# SwitchRegTestBoard.net
KiCad netlist of a schematic drawn in EAGLE
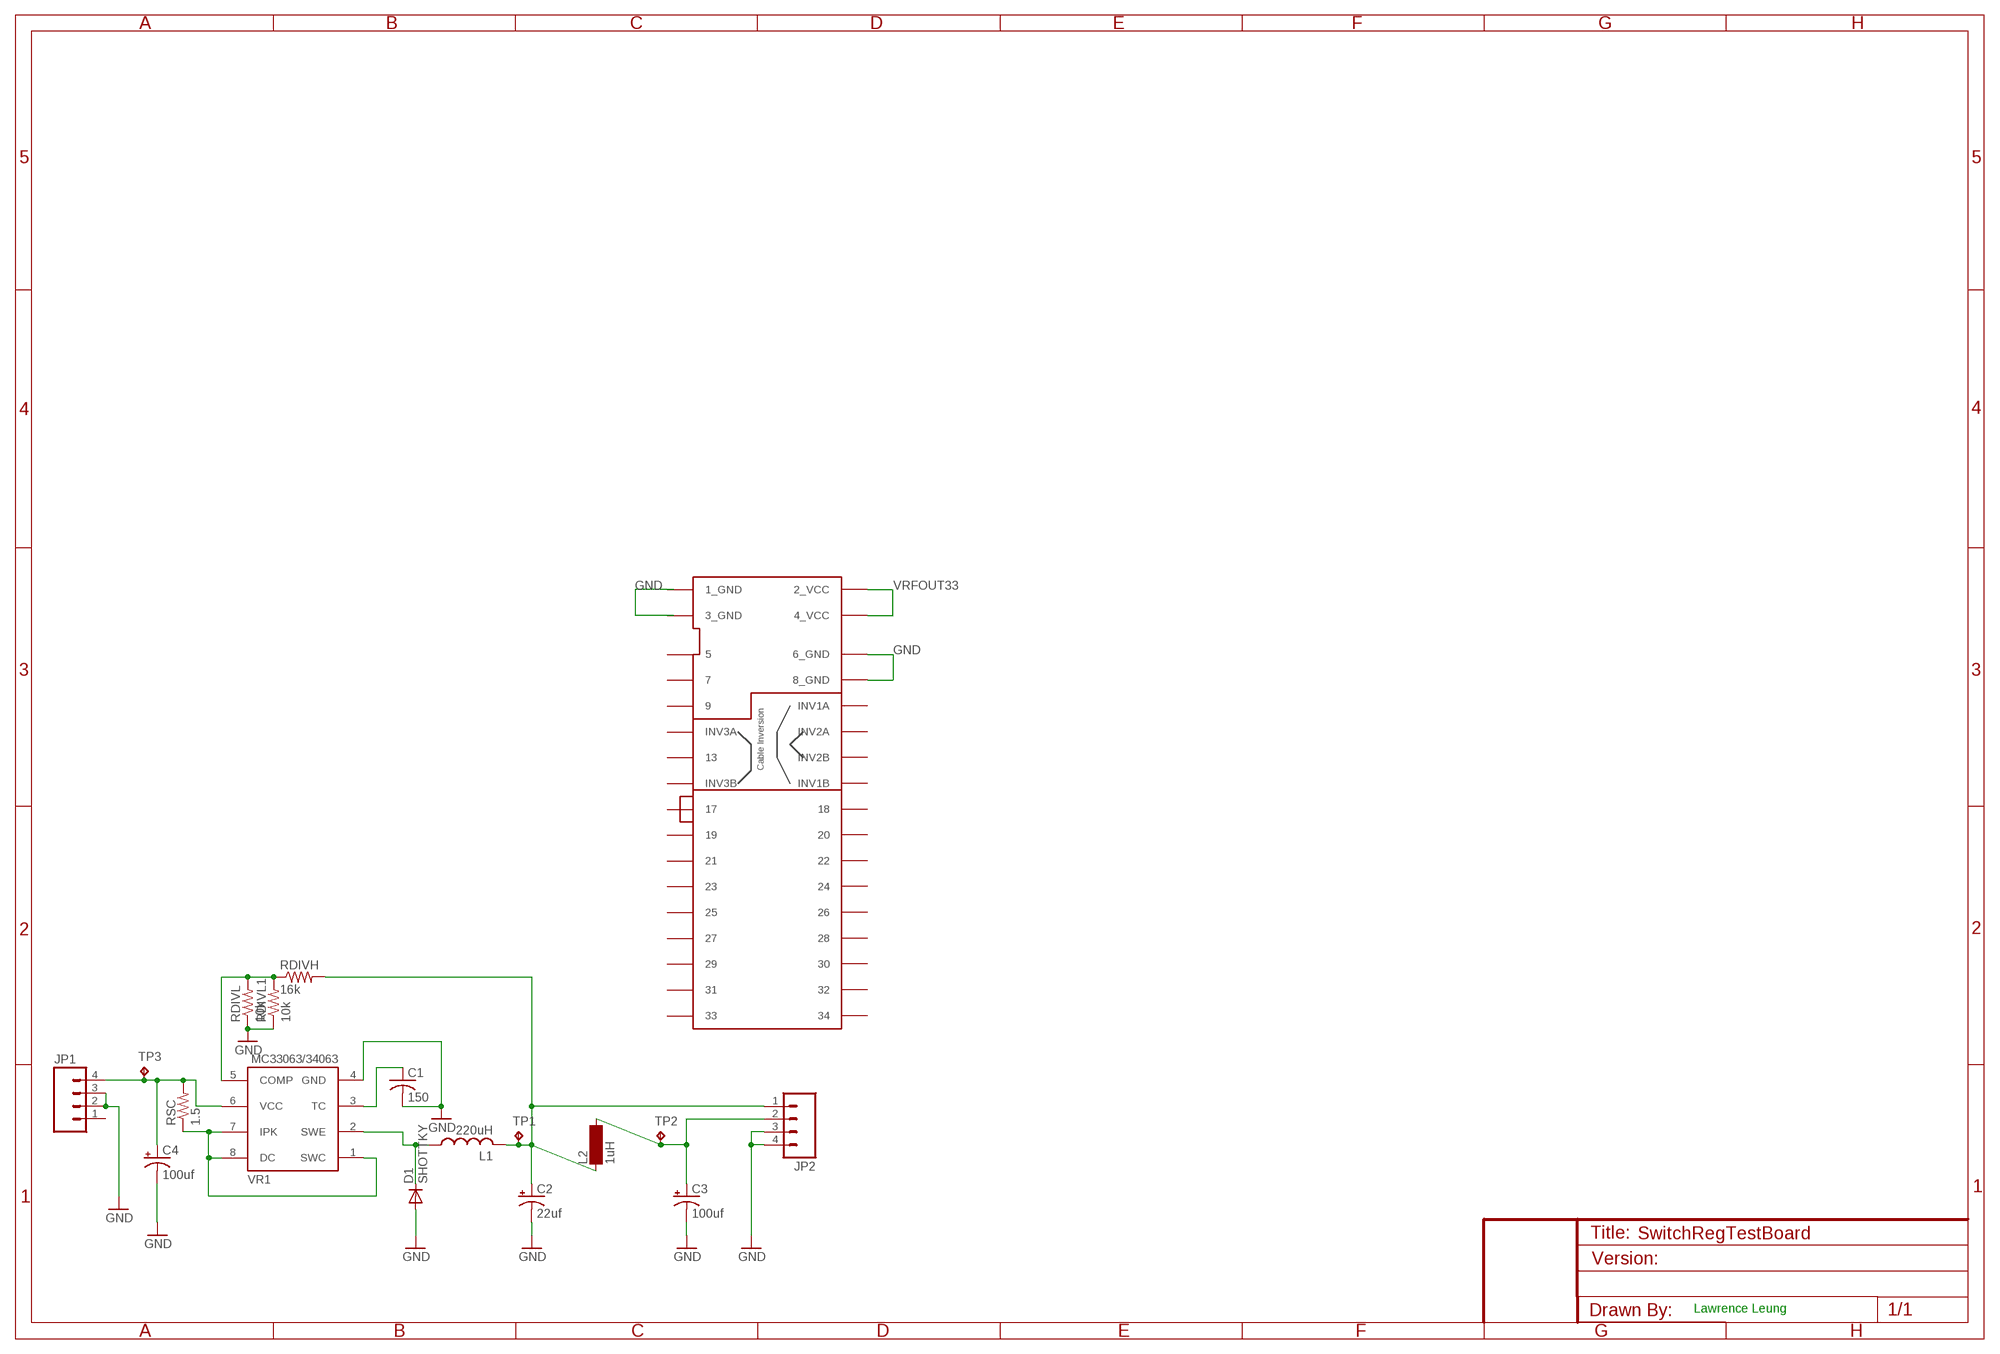
[diagram p0: schematic, sheet 1]

(export (version "E")
  (design (tool "Eeschema 10.0.6"))
  (components
    (comp (ref "C1")
      (value "150")
      (footprint "eagle-import:C0603")
      (libsource (lib "eagle-import") (part "C-USC0603"))
    )
    (comp (ref "C2")
      (value "22uf")
      (footprint "eagle-import:PANASONIC_C")
      (libsource (lib "eagle-import") (part "CPOL-USC"))
    )
    (comp (ref "C3")
      (value "100uf")
      (footprint "eagle-import:PANASONIC_C")
      (libsource (lib "eagle-import") (part "CPOL-USC"))
    )
    (comp (ref "C4")
      (value "100uf")
      (footprint "eagle-import:PANASONIC_C")
      (libsource (lib "eagle-import") (part "CPOL-USC"))
    )
    (comp (ref "D1")
      (value "SHOTTKY")
      (footprint "eagle-import:SOD-123")
      (libsource (lib "eagle-import") (part "DIODE-SOD-123"))
    )
    (comp (ref "JP1")
      (value "HEADER1X4SMD_LONGPADS")
      (footprint "eagle-import:1X04-SMD-LONG")
      (libsource (lib "eagle-import") (part "HEADER1X4SMD_LONGPADS"))
    )
    (comp (ref "JP2")
      (value "HEADER1X4SMD_LONGPADS")
      (footprint "eagle-import:1X04-SMD-LONG")
      (libsource (lib "eagle-import") (part "HEADER1X4SMD_LONGPADS"))
    )
    (comp (ref "L1")
      (value "220uH")
      (footprint "eagle-import:L0707MM")
      (libsource (lib "eagle-import") (part "L-USL0707MM"))
    )
    (comp (ref "L2")
      (value "1uH")
      (footprint "eagle-import:SM-NE29")
      (libsource (lib "eagle-import") (part "SM-NE29"))
    )
    (comp (ref "RDIVH")
      (value "16k")
      (footprint "eagle-import:R0805")
      (libsource (lib "eagle-import") (part "R-US_R0805"))
    )
    (comp (ref "RDIVL")
      (value "10k")
      (footprint "eagle-import:R0805")
      (libsource (lib "eagle-import") (part "R-US_R0805"))
    )
    (comp (ref "RDIVL1")
      (value "10k")
      (footprint "eagle-import:R0805")
      (libsource (lib "eagle-import") (part "R-US_R0805"))
    )
    (comp (ref "RSC")
      (value "1.5")
      (footprint "eagle-import:R1206")
      (libsource (lib "eagle-import") (part "R-US_R1206"))
    )
    (comp (ref "TP1")
      (value "TPTP10R")
      (footprint "eagle-import:TP10R")
      (libsource (lib "eagle-import") (part "TPTP10R"))
    )
    (comp (ref "TP2")
      (value "TPTP10R")
      (footprint "eagle-import:TP10R")
      (libsource (lib "eagle-import") (part "TPTP10R"))
    )
    (comp (ref "TP3")
      (value "TPTP10R")
      (footprint "eagle-import:TP10R")
      (libsource (lib "eagle-import") (part "TPTP10R"))
    )
    (comp (ref "U$1")
      (value "HEADER-525IDEB")
      (footprint "eagle-import:HEADER-525IDEB")
      (libsource (lib "eagle-import") (part "HEADER-525IDEB"))
    )
    (comp (ref "VR1")
      (value "MC34063AD")
      (footprint "eagle-import:SO08")
      (libsource (lib "eagle-import") (part "MC33063/MC34063D"))
    )
  )
  (nets
    (net (code "1") (name "/1_GND") (class "Default")
      (node (ref "U$1") (pin "1_GND") (pinfunction "1_GND_1_GND") (pintype "power_in"))
    )
    (net (code "2") (name "/3_GND") (class "Default")
      (node (ref "U$1") (pin "3_KEY_NC") (pinfunction "3_GND_3_KEY_NC") (pintype "power_in"))
    )
    (net (code "3") (name "/VRFOUT33") (class "Default")
      (node (ref "C3") (pin "+") (pinfunction "+_+") (pintype "passive"))
      (node (ref "JP2") (pin "2") (pinfunction "2_2") (pintype "passive"))
      (node (ref "L2") (pin "2") (pinfunction "2_2") (pintype "passive"))
      (node (ref "TP2") (pin "TP") (pinfunction "TP_TP") (pintype "input"))
      (node (ref "U$1") (pin "2_DCD") (pinfunction "2_VCC_2_DCD") (pintype "power_in"))
      (node (ref "U$1") (pin "4_DS3") (pinfunction "4_VCC_4_DS3") (pintype "power_in"))
    )
    (net (code "4") (name "GND") (class "Default")
      (node (ref "C1") (pin "2") (pinfunction "2_2") (pintype "passive"))
      (node (ref "C2") (pin "-") (pinfunction "-_-") (pintype "passive"))
      (node (ref "C3") (pin "-") (pinfunction "-_-") (pintype "passive"))
      (node (ref "C4") (pin "-") (pinfunction "-_-") (pintype "passive"))
      (node (ref "D1") (pin "A") (pinfunction "A_A") (pintype "passive"))
      (node (ref "JP1") (pin "2") (pinfunction "2_2") (pintype "passive"))
      (node (ref "JP1") (pin "3") (pinfunction "3_3") (pintype "passive"))
      (node (ref "JP2") (pin "3") (pinfunction "3_3") (pintype "passive"))
      (node (ref "JP2") (pin "4") (pinfunction "4_4") (pintype "passive"))
      (node (ref "RDIVL") (pin "1") (pinfunction "1_1") (pintype "passive"))
      (node (ref "RDIVL1") (pin "1") (pinfunction "1_1") (pintype "passive"))
      (node (ref "U$1") (pin "6_INUSE") (pinfunction "6_GND_6_INUSE") (pintype "power_in"))
      (node (ref "U$1") (pin "8_INDEX") (pinfunction "8_GND_8_INDEX") (pintype "power_in"))
      (node (ref "VR1") (pin "4") (pinfunction "GND_4") (pintype "power_in"))
    )
    (net (code "5") (name "Net-(C2-Pad+)") (class "Default")
      (node (ref "C2") (pin "+") (pinfunction "+_+") (pintype "passive"))
      (node (ref "JP2") (pin "1") (pinfunction "1_1") (pintype "passive"))
      (node (ref "L1") (pin "2") (pinfunction "2_2") (pintype "passive"))
      (node (ref "L2") (pin "1") (pinfunction "1_1") (pintype "passive"))
      (node (ref "RDIVH") (pin "2") (pinfunction "2_2") (pintype "passive"))
      (node (ref "TP1") (pin "TP") (pinfunction "TP_TP") (pintype "input"))
    )
    (net (code "6") (name "Net-(VR1-COMP)") (class "Default")
      (node (ref "RDIVH") (pin "1") (pinfunction "1_1") (pintype "passive"))
      (node (ref "RDIVL") (pin "2") (pinfunction "2_2") (pintype "passive"))
      (node (ref "RDIVL1") (pin "2") (pinfunction "2_2") (pintype "passive"))
      (node (ref "VR1") (pin "5") (pinfunction "COMP_5") (pintype "input"))
    )
    (net (code "7") (name "Net-(VR1-DC)") (class "Default")
      (node (ref "RSC") (pin "1") (pinfunction "1_1") (pintype "passive"))
      (node (ref "VR1") (pin "1") (pinfunction "SWC_1") (pintype "input"))
      (node (ref "VR1") (pin "7") (pinfunction "IPK_7") (pintype "bidirectional"))
      (node (ref "VR1") (pin "8") (pinfunction "DC_8") (pintype "input"))
    )
    (net (code "8") (name "Net-(VR1-SWE)") (class "Default")
      (node (ref "D1") (pin "C") (pinfunction "C_C") (pintype "passive"))
      (node (ref "L1") (pin "1") (pinfunction "1_1") (pintype "passive"))
      (node (ref "VR1") (pin "2") (pinfunction "SWE_2") (pintype "input"))
    )
    (net (code "9") (name "Net-(VR1-TC)") (class "Default")
      (node (ref "C1") (pin "1") (pinfunction "1_1") (pintype "passive"))
      (node (ref "VR1") (pin "3") (pinfunction "TC_3") (pintype "input"))
    )
    (net (code "10") (name "Net-(VR1-VCC)") (class "Default")
      (node (ref "C4") (pin "+") (pinfunction "+_+") (pintype "passive"))
      (node (ref "JP1") (pin "4") (pinfunction "4_4") (pintype "passive"))
      (node (ref "RSC") (pin "2") (pinfunction "2_2") (pintype "passive"))
      (node (ref "TP3") (pin "TP") (pinfunction "TP_TP") (pintype "input"))
      (node (ref "VR1") (pin "6") (pinfunction "VCC_6") (pintype "power_in"))
    )
    (net (code "11") (name "unconnected-(JP1-Pad1)") (class "Default")
      (node (ref "JP1") (pin "1") (pinfunction "1_1") (pintype "passive"))
    )
    (net (code "12") (name "unconnected-(U$1-5-Pad5_GND)") (class "Default")
      (node (ref "U$1") (pin "5_GND") (pinfunction "5_5_GND") (pintype "bidirectional"))
    )
    (net (code "13") (name "unconnected-(U$1-7-Pad7_NC)") (class "Default")
      (node (ref "U$1") (pin "7_NC") (pinfunction "7_7_NC") (pintype "bidirectional"))
    )
    (net (code "14") (name "unconnected-(U$1-9-Pad9_GND)") (class "Default")
      (node (ref "U$1") (pin "9_GND") (pinfunction "9_9_GND") (pintype "bidirectional"))
    )
    (net (code "15") (name "unconnected-(U$1-13-Pad13_NC)") (class "Default")
      (node (ref "U$1") (pin "13_NC") (pinfunction "13_13_NC") (pintype "bidirectional"))
    )
    (net (code "16") (name "unconnected-(U$1-17-Pad17_MSEN1)") (class "Default")
      (node (ref "U$1") (pin "17_MSEN1") (pinfunction "17_17_MSEN1") (pintype "bidirectional"))
    )
    (net (code "17") (name "unconnected-(U$1-18-Pad18_DIR)") (class "Default")
      (node (ref "U$1") (pin "18_DIR") (pinfunction "18_18_DIR") (pintype "bidirectional"))
    )
    (net (code "18") (name "unconnected-(U$1-19-Pad19_GND)") (class "Default")
      (node (ref "U$1") (pin "19_GND") (pinfunction "19_19_GND") (pintype "bidirectional"))
    )
    (net (code "19") (name "unconnected-(U$1-20-Pad20_STEP)") (class "Default")
      (node (ref "U$1") (pin "20_STEP") (pinfunction "20_20_STEP") (pintype "bidirectional"))
    )
    (net (code "20") (name "unconnected-(U$1-21-Pad21_FD_WR_DAT_L)") (class "Default")
      (node (ref "U$1") (pin "21_FD_WR_DAT_L") (pinfunction "21_21_FD_WR_DAT_L") (pintype "bidirectional"))
    )
    (net (code "21") (name "unconnected-(U$1-22-Pad22_WDATE)") (class "Default")
      (node (ref "U$1") (pin "22_WDATE") (pinfunction "22_22_WDATE") (pintype "bidirectional"))
    )
    (net (code "22") (name "unconnected-(U$1-23-Pad23_GND)") (class "Default")
      (node (ref "U$1") (pin "23_GND") (pinfunction "23_23_GND") (pintype "bidirectional"))
    )
    (net (code "23") (name "unconnected-(U$1-24-Pad24_WGATE)") (class "Default")
      (node (ref "U$1") (pin "24_WGATE") (pinfunction "24_24_WGATE") (pintype "bidirectional"))
    )
    (net (code "24") (name "unconnected-(U$1-25-Pad25_GND)") (class "Default")
      (node (ref "U$1") (pin "25_GND") (pinfunction "25_25_GND") (pintype "bidirectional"))
    )
    (net (code "25") (name "unconnected-(U$1-26-Pad26_TRK0)") (class "Default")
      (node (ref "U$1") (pin "26_TRK0") (pinfunction "26_26_TRK0") (pintype "bidirectional"))
    )
    (net (code "26") (name "unconnected-(U$1-27-Pad27_MSEN0)") (class "Default")
      (node (ref "U$1") (pin "27_MSEN0") (pinfunction "27_27_MSEN0") (pintype "bidirectional"))
    )
    (net (code "27") (name "unconnected-(U$1-28-Pad28_WPT)") (class "Default")
      (node (ref "U$1") (pin "28_WPT") (pinfunction "28_28_WPT") (pintype "bidirectional"))
    )
    (net (code "28") (name "unconnected-(U$1-29-Pad29_GND)") (class "Default")
      (node (ref "U$1") (pin "29_GND") (pinfunction "29_29_GND") (pintype "bidirectional"))
    )
    (net (code "29") (name "unconnected-(U$1-30-Pad30_RDATA)") (class "Default")
      (node (ref "U$1") (pin "30_RDATA") (pinfunction "30_30_RDATA") (pintype "bidirectional"))
    )
    (net (code "30") (name "unconnected-(U$1-31-Pad31_GND)") (class "Default")
      (node (ref "U$1") (pin "31_GND") (pinfunction "31_31_GND") (pintype "bidirectional"))
    )
    (net (code "31") (name "unconnected-(U$1-32-Pad32SIDE1)") (class "Default")
      (node (ref "U$1") (pin "32SIDE1") (pinfunction "32_32SIDE1") (pintype "bidirectional"))
    )
    (net (code "32") (name "unconnected-(U$1-33-Pad33_GND)") (class "Default")
      (node (ref "U$1") (pin "33_GND") (pinfunction "33_33_GND") (pintype "bidirectional"))
    )
    (net (code "33") (name "unconnected-(U$1-34-Pad34_RDY)") (class "Default")
      (node (ref "U$1") (pin "34_RDY") (pinfunction "34_34_RDY") (pintype "bidirectional"))
    )
    (net (code "34") (name "unconnected-(U$1-INV1A-Pad10_DS0_MEA_MEB)") (class "Default")
      (node (ref "U$1") (pin "10_DS0_MEA_MEB") (pinfunction "INV1A_10_DS0_MEA_MEB") (pintype "bidirectional"))
    )
    (net (code "35") (name "unconnected-(U$1-INV1B-Pad16_MTRON_MEB_MEA)") (class "Default")
      (node (ref "U$1") (pin "16_MTRON_MEB_MEA") (pinfunction "INV1B_16_MTRON_MEB_MEA") (pintype "bidirectional"))
    )
    (net (code "36") (name "unconnected-(U$1-INV2A-Pad12_DS1_DSB_DSA)") (class "Default")
      (node (ref "U$1") (pin "12_DS1_DSB_DSA") (pinfunction "INV2A_12_DS1_DSB_DSA") (pintype "bidirectional"))
    )
    (net (code "37") (name "unconnected-(U$1-INV2B-Pad14_DS2_DSA_DSB)") (class "Default")
      (node (ref "U$1") (pin "14_DS2_DSA_DSB") (pinfunction "INV2B_14_DS2_DSA_DSB") (pintype "bidirectional"))
    )
    (net (code "38") (name "unconnected-(U$1-INV3A-Pad11_GND)") (class "Default")
      (node (ref "U$1") (pin "11_GND") (pinfunction "INV3A_11_GND") (pintype "bidirectional"))
    )
    (net (code "39") (name "unconnected-(U$1-INV3B-Pad15_GND)") (class "Default")
      (node (ref "U$1") (pin "15_GND") (pinfunction "INV3B_15_GND") (pintype "bidirectional"))
    )
  )
)
